# dengen1.net
KiCad netlist of a schematic drawn in EAGLE
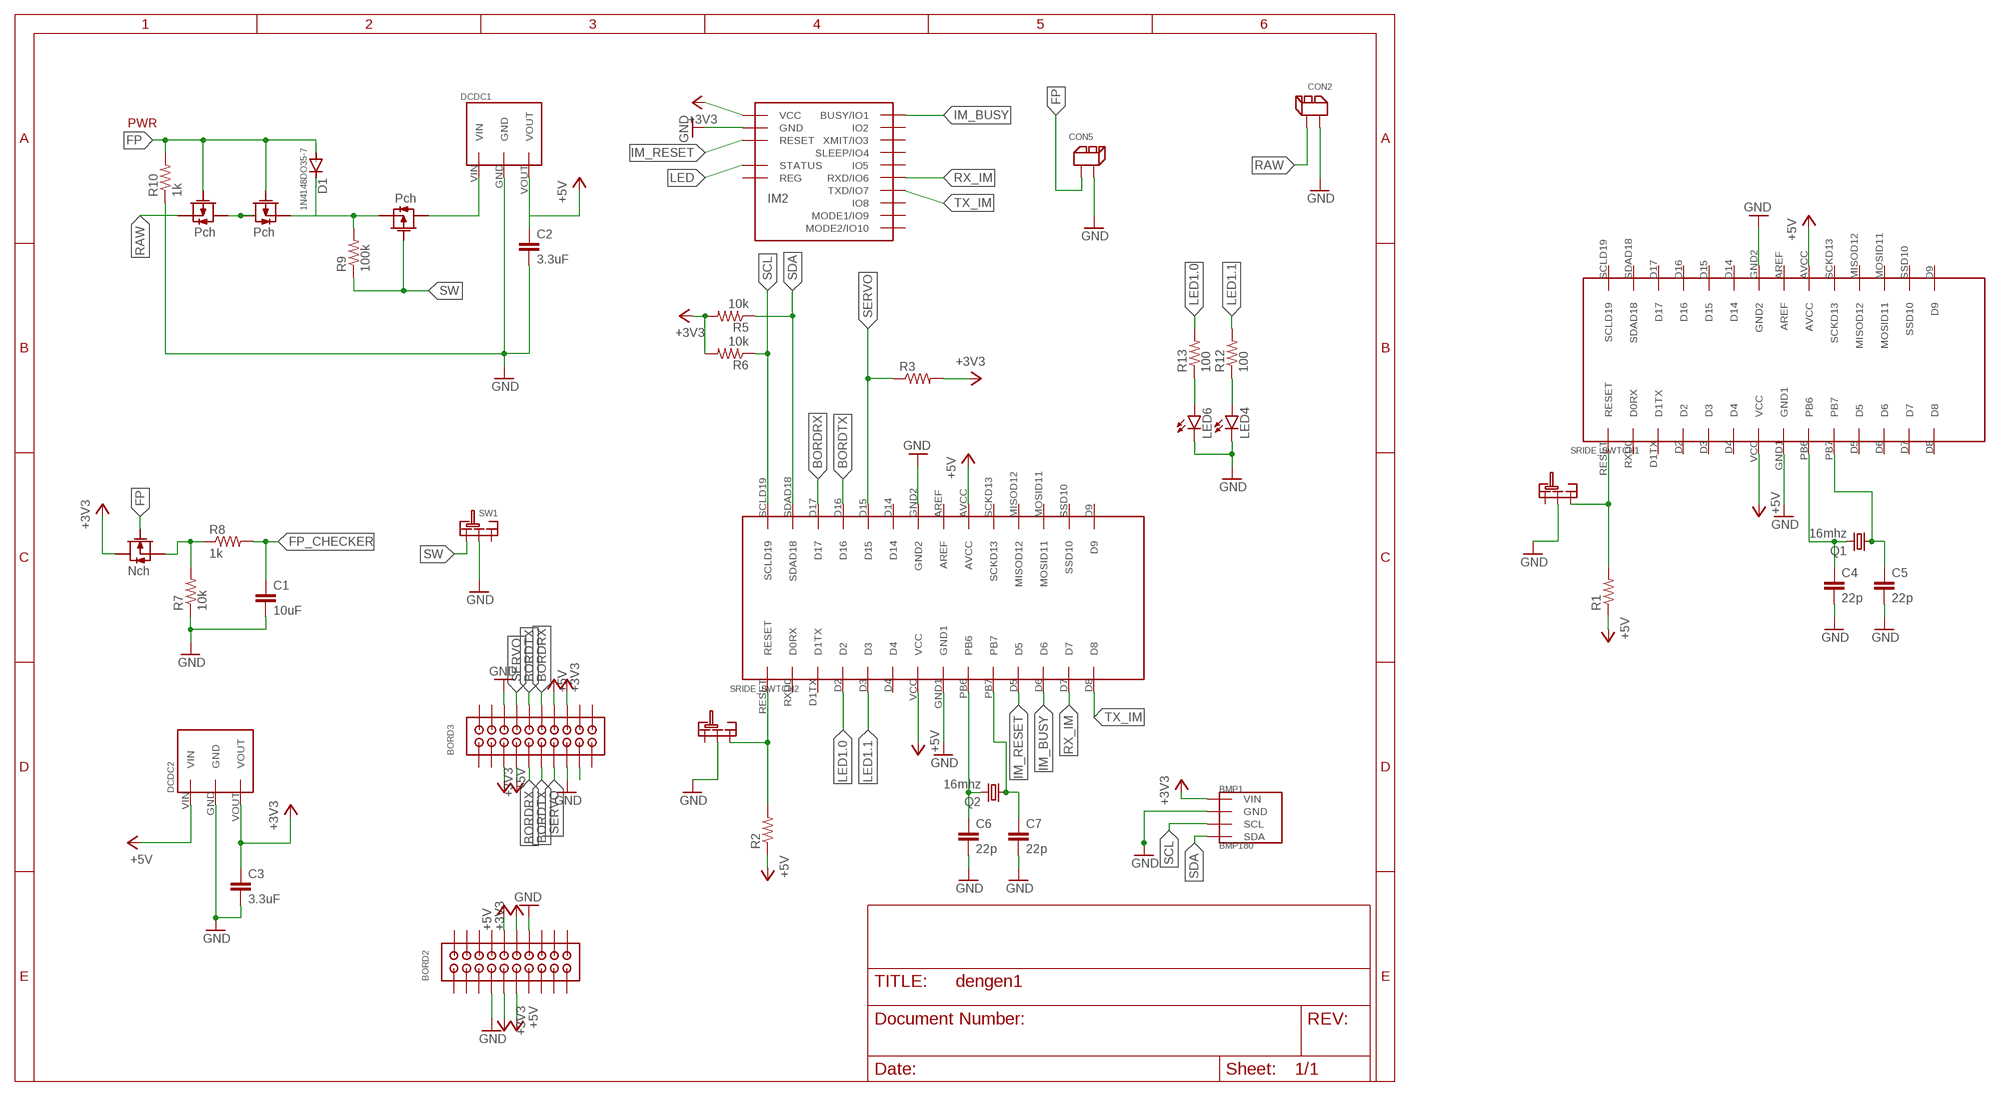
[diagram p0: schematic, sheet 1]

(export (version "E")
  (design (tool "Eeschema 10.0.6"))
  (components
    (comp (ref "BMP1")
      (value "BMP180")
      (footprint "eagle-import:GY-68")
      (libsource (lib "eagle-import") (part "BMP180"))
    )
    (comp (ref "BORD2")
      (value "2X10")
      (footprint "eagle-import:2X10")
      (libsource (lib "eagle-import") (part "2X10"))
    )
    (comp (ref "BORD3")
      (value "2X10")
      (footprint "eagle-import:2X10")
      (libsource (lib "eagle-import") (part "2X10"))
    )
    (comp (ref "C1")
      (value "10uF")
      (footprint "eagle-import:C025-024X044")
      (libsource (lib "eagle-import") (part "C-EU025-024X044"))
    )
    (comp (ref "C2")
      (value "3.3uF")
      (footprint "eagle-import:C025-024X044")
      (libsource (lib "eagle-import") (part "C-EU025-024X044"))
    )
    (comp (ref "C3")
      (value "3.3uF")
      (footprint "eagle-import:C025-024X044")
      (libsource (lib "eagle-import") (part "C-EU025-024X044"))
    )
    (comp (ref "C4")
      (value "22p")
      (footprint "eagle-import:C025-024X044")
      (libsource (lib "eagle-import") (part "C-EU025-024X044"))
    )
    (comp (ref "C5")
      (value "22p")
      (footprint "eagle-import:C025-024X044")
      (libsource (lib "eagle-import") (part "C-EU025-024X044"))
    )
    (comp (ref "C6")
      (value "22p")
      (footprint "eagle-import:C025-024X044")
      (libsource (lib "eagle-import") (part "C-EU025-024X044"))
    )
    (comp (ref "C7")
      (value "22p")
      (footprint "eagle-import:C025-024X044")
      (libsource (lib "eagle-import") (part "C-EU025-024X044"))
    )
    (comp (ref "CON2")
      (value "2PIN")
      (footprint "eagle-import:2PIN")
      (libsource (lib "eagle-import") (part "2PIN"))
    )
    (comp (ref "CON5")
      (value "2PIN")
      (footprint "eagle-import:2PIN")
      (libsource (lib "eagle-import") (part "2PIN"))
    )
    (comp (ref "D1")
      (value "1N4148DO35-7")
      (footprint "eagle-import:DO35-7")
      (libsource (lib "eagle-import") (part "1N4148DO35-7"))
    )
    (comp (ref "DCDC1")
      (value "5V1A_M78AR05-1")
      (footprint "eagle-import:5V1A_M78AR05-1")
      (libsource (lib "eagle-import") (part "5V1A_M78AR05-1"))
    )
    (comp (ref "DCDC2")
      (value "3.3V1A_M78AR033-1")
      (footprint "eagle-import:3.3V1A_M78AR033-1")
      (libsource (lib "eagle-import") (part "3.3V1A_M78AR033-1"))
    )
    (comp (ref "IM2")
      (value "IM920_IM920C")
      (footprint "eagle-import:IM920_IM920C")
      (libsource (lib "eagle-import") (part "IM920_IM920C"))
    )
    (comp (ref "LED4")
      (value "LED5MM")
      (footprint "eagle-import:LED5MM")
      (libsource (lib "eagle-import") (part "LED5MM"))
    )
    (comp (ref "LED6")
      (value "LED5MM")
      (footprint "eagle-import:LED5MM")
      (libsource (lib "eagle-import") (part "LED5MM"))
    )
    (comp (ref "Q1")
      (value "16mhz")
      (footprint "eagle-import:HC49_S")
      (libsource (lib "eagle-import") (part "CRYSTALHC49S"))
    )
    (comp (ref "Q2")
      (value "16mhz")
      (footprint "eagle-import:HC49_S")
      (libsource (lib "eagle-import") (part "CRYSTALHC49S"))
    )
    (comp (ref "R1")
      (value "R-US_0204/7")
      (footprint "eagle-import:0204_7")
      (libsource (lib "eagle-import") (part "R-US_0204/7"))
    )
    (comp (ref "R2")
      (value "R-US_0204/7")
      (footprint "eagle-import:0204_7")
      (libsource (lib "eagle-import") (part "R-US_0204/7"))
    )
    (comp (ref "R3")
      (value "R-US_0204/7")
      (footprint "eagle-import:0204_7")
      (libsource (lib "eagle-import") (part "R-US_0204/7"))
    )
    (comp (ref "R5")
      (value "10k")
      (footprint "eagle-import:0204_7")
      (libsource (lib "eagle-import") (part "R-US_0204/7"))
    )
    (comp (ref "R6")
      (value "10k")
      (footprint "eagle-import:0204_7")
      (libsource (lib "eagle-import") (part "R-US_0204/7"))
    )
    (comp (ref "R7")
      (value "10k")
      (footprint "eagle-import:0204_7")
      (libsource (lib "eagle-import") (part "R-US_0204/7"))
    )
    (comp (ref "R8")
      (value "1k")
      (footprint "eagle-import:0204_7")
      (libsource (lib "eagle-import") (part "R-US_0204/7"))
    )
    (comp (ref "R9")
      (value "100k")
      (footprint "eagle-import:0204_7")
      (libsource (lib "eagle-import") (part "R-US_0204/7"))
    )
    (comp (ref "R10")
      (value "1k")
      (footprint "eagle-import:0204_7")
      (libsource (lib "eagle-import") (part "R-US_0204/7"))
    )
    (comp (ref "R12")
      (value "100")
      (footprint "eagle-import:0204_7")
      (libsource (lib "eagle-import") (part "R-US_0204/7"))
    )
    (comp (ref "R13")
      (value "100")
      (footprint "eagle-import:0204_7")
      (libsource (lib "eagle-import") (part "R-US_0204/7"))
    )
    (comp (ref "SRIDE_SWTCH1")
      (value "SRIDE_SWITCH")
      (footprint "eagle-import:SRIDE_SWITCH")
      (libsource (lib "eagle-import") (part "SRIDE_SWITCH"))
    )
    (comp (ref "SRIDE_SWTCH2")
      (value "SRIDE_SWITCH")
      (footprint "eagle-import:SRIDE_SWITCH")
      (libsource (lib "eagle-import") (part "SRIDE_SWITCH"))
    )
    (comp (ref "SW1")
      (value "SRIDE_SWITCH")
      (footprint "eagle-import:SRIDE_SWITCH")
      (libsource (lib "eagle-import") (part "SRIDE_SWITCH"))
    )
    (comp (ref "U$1")
      (value "ATMEGA238P")
      (footprint "eagle-import:ATMEGA328P")
      (libsource (lib "eagle-import") (part "ATMEGA238P"))
    )
    (comp (ref "U$2")
      (value "2SJ681-PCH")
      (footprint "eagle-import:2SJ681")
      (libsource (lib "eagle-import") (part "2SJ681-PCH"))
    )
    (comp (ref "U$3")
      (value "2SK4017-NCH")
      (footprint "eagle-import:2SK4017")
      (libsource (lib "eagle-import") (part "2SK4017-NCH"))
    )
    (comp (ref "U$4")
      (value "2SJ681-PCH")
      (footprint "eagle-import:2SJ681")
      (libsource (lib "eagle-import") (part "2SJ681-PCH"))
    )
    (comp (ref "U$5")
      (value "2SJ681-PCH")
      (footprint "eagle-import:2SJ681")
      (libsource (lib "eagle-import") (part "2SJ681-PCH"))
    )
    (comp (ref "U$6")
      (value "ATMEGA238P")
      (footprint "eagle-import:ATMEGA328P")
      (libsource (lib "eagle-import") (part "ATMEGA238P"))
    )
  )
  (nets
    (net (code "1") (name "+3V3") (class "Default")
      (node (ref "BMP1") (pin "P1") (pinfunction "VIN_P1") (pintype "bidirectional"))
      (node (ref "BORD2") (pin "P$12") (pinfunction "P$12_P$12") (pintype "bidirectional"))
      (node (ref "BORD2") (pin "P$9") (pinfunction "P$9_P$9") (pintype "bidirectional"))
      (node (ref "BORD3") (pin "P$16") (pinfunction "P$16_P$16") (pintype "bidirectional"))
      (node (ref "BORD3") (pin "P$5") (pinfunction "P$5_P$5") (pintype "bidirectional"))
      (node (ref "C3") (pin "1") (pinfunction "1_1") (pintype "passive"))
      (node (ref "DCDC2") (pin "VOUT") (pinfunction "VOUT_VOUT") (pintype "bidirectional"))
      (node (ref "IM2") (pin "$P17") (pinfunction "VCC_$P17") (pintype "bidirectional"))
      (node (ref "R3") (pin "2") (pinfunction "2_2") (pintype "passive"))
      (node (ref "R5") (pin "2") (pinfunction "2_2") (pintype "passive"))
      (node (ref "R6") (pin "2") (pinfunction "2_2") (pintype "passive"))
      (node (ref "U$3") (pin "DRAIN") (pinfunction "DRAIN_DRAIN") (pintype "bidirectional"))
    )
    (net (code "2") (name "+5V") (class "Default")
      (node (ref "BORD2") (pin "P$10") (pinfunction "P$10_P$10") (pintype "bidirectional"))
      (node (ref "BORD2") (pin "P$11") (pinfunction "P$11_P$11") (pintype "bidirectional"))
      (node (ref "BORD3") (pin "P$14") (pinfunction "P$14_P$14") (pintype "bidirectional"))
      (node (ref "BORD3") (pin "P$7") (pinfunction "P$7_P$7") (pintype "bidirectional"))
      (node (ref "C2") (pin "1") (pinfunction "1_1") (pintype "passive"))
      (node (ref "DCDC1") (pin "VOUT") (pinfunction "VOUT_VOUT") (pintype "bidirectional"))
      (node (ref "DCDC2") (pin "VIN") (pinfunction "VIN_VIN") (pintype "bidirectional"))
      (node (ref "R1") (pin "1") (pinfunction "1_1") (pintype "passive"))
      (node (ref "R2") (pin "1") (pinfunction "1_1") (pintype "passive"))
      (node (ref "U$1") (pin "AVCC") (pinfunction "AVCC_AVCC") (pintype "bidirectional"))
      (node (ref "U$1") (pin "VCC") (pinfunction "VCC_VCC") (pintype "bidirectional"))
      (node (ref "U$6") (pin "AVCC") (pinfunction "AVCC_AVCC") (pintype "bidirectional"))
      (node (ref "U$6") (pin "VCC") (pinfunction "VCC_VCC") (pintype "bidirectional"))
    )
    (net (code "3") (name "BORDRX") (class "Default")
      (node (ref "BORD3") (pin "P$12") (pinfunction "P$12_P$12") (pintype "bidirectional"))
      (node (ref "BORD3") (pin "P$9") (pinfunction "P$9_P$9") (pintype "bidirectional"))
      (node (ref "U$6") (pin "D17") (pinfunction "D17_D17") (pintype "bidirectional"))
    )
    (net (code "4") (name "BORDTX") (class "Default")
      (node (ref "BORD3") (pin "P$10") (pinfunction "P$10_P$10") (pintype "bidirectional"))
      (node (ref "BORD3") (pin "P$11") (pinfunction "P$11_P$11") (pintype "bidirectional"))
      (node (ref "U$6") (pin "D16") (pinfunction "D16_D16") (pintype "bidirectional"))
    )
    (net (code "5") (name "FP") (class "Default")
      (node (ref "CON5") (pin "P$1") (pinfunction "P$1_P$1") (pintype "bidirectional"))
      (node (ref "D1") (pin "A") (pinfunction "A_A") (pintype "passive"))
      (node (ref "R10") (pin "2") (pinfunction "2_2") (pintype "passive"))
      (node (ref "U$2") (pin "GATE") (pinfunction "GATE_GATE") (pintype "bidirectional"))
      (node (ref "U$3") (pin "GATE") (pinfunction "GATE_GATE") (pintype "bidirectional"))
      (node (ref "U$4") (pin "GATE") (pinfunction "GATE_GATE") (pintype "bidirectional"))
    )
    (net (code "6") (name "FP_CHECKER") (class "Default")
      (node (ref "C1") (pin "1") (pinfunction "1_1") (pintype "passive"))
      (node (ref "R8") (pin "2") (pinfunction "2_2") (pintype "passive"))
    )
    (net (code "7") (name "GND") (class "Default")
      (node (ref "BMP1") (pin "P2") (pinfunction "GND_P2") (pintype "bidirectional"))
      (node (ref "BORD2") (pin "P$14") (pinfunction "P$14_P$14") (pintype "bidirectional"))
      (node (ref "BORD2") (pin "P$7") (pinfunction "P$7_P$7") (pintype "bidirectional"))
      (node (ref "BORD3") (pin "P$15") (pinfunction "P$15_P$15") (pintype "bidirectional"))
      (node (ref "BORD3") (pin "P$6") (pinfunction "P$6_P$6") (pintype "bidirectional"))
      (node (ref "C1") (pin "2") (pinfunction "2_2") (pintype "passive"))
      (node (ref "C2") (pin "2") (pinfunction "2_2") (pintype "passive"))
      (node (ref "C3") (pin "2") (pinfunction "2_2") (pintype "passive"))
      (node (ref "C4") (pin "2") (pinfunction "2_2") (pintype "passive"))
      (node (ref "C5") (pin "2") (pinfunction "2_2") (pintype "passive"))
      (node (ref "C6") (pin "2") (pinfunction "2_2") (pintype "passive"))
      (node (ref "C7") (pin "2") (pinfunction "2_2") (pintype "passive"))
      (node (ref "CON2") (pin "P$1") (pinfunction "P$1_P$1") (pintype "bidirectional"))
      (node (ref "CON5") (pin "P$2") (pinfunction "P$2_P$2") (pintype "bidirectional"))
      (node (ref "DCDC1") (pin "GND") (pinfunction "GND_GND") (pintype "bidirectional"))
      (node (ref "DCDC2") (pin "GND") (pinfunction "GND_GND") (pintype "bidirectional"))
      (node (ref "IM2") (pin "$P18") (pinfunction "GND_$P18") (pintype "bidirectional"))
      (node (ref "LED4") (pin "K") (pinfunction "C_K") (pintype "passive"))
      (node (ref "LED6") (pin "K") (pinfunction "C_K") (pintype "passive"))
      (node (ref "R10") (pin "1") (pinfunction "1_1") (pintype "passive"))
      (node (ref "R7") (pin "1") (pinfunction "1_1") (pintype "passive"))
      (node (ref "SRIDE_SWTCH1") (pin "LR") (pinfunction "LR_LR") (pintype "bidirectional"))
      (node (ref "SRIDE_SWTCH2") (pin "LR") (pinfunction "LR_LR") (pintype "bidirectional"))
      (node (ref "SW1") (pin "LR") (pinfunction "LR_LR") (pintype "bidirectional"))
      (node (ref "U$1") (pin "GND1") (pinfunction "GND1_GND1") (pintype "bidirectional"))
      (node (ref "U$1") (pin "GND2") (pinfunction "GND2_GND2") (pintype "bidirectional"))
      (node (ref "U$6") (pin "GND1") (pinfunction "GND1_GND1") (pintype "bidirectional"))
      (node (ref "U$6") (pin "GND2") (pinfunction "GND2_GND2") (pintype "bidirectional"))
    )
    (net (code "8") (name "IM_BUSY") (class "Default")
      (node (ref "IM2") (pin "$P1") (pinfunction "BUSY/IO1_$P1") (pintype "bidirectional"))
      (node (ref "U$6") (pin "D6") (pinfunction "D6_D6") (pintype "bidirectional"))
    )
    (net (code "9") (name "IM_RESET") (class "Default")
      (node (ref "IM2") (pin "$P19") (pinfunction "RESET_$P19") (pintype "bidirectional"))
      (node (ref "U$6") (pin "D5") (pinfunction "D5_D5") (pintype "bidirectional"))
    )
    (net (code "10") (name "LED") (class "Default")
      (node (ref "IM2") (pin "$P15") (pinfunction "STATUS_$P15") (pintype "bidirectional"))
    )
    (net (code "11") (name "LED1.0") (class "Default")
      (node (ref "R13") (pin "2") (pinfunction "2_2") (pintype "passive"))
      (node (ref "U$6") (pin "D2") (pinfunction "D2_D2") (pintype "bidirectional"))
    )
    (net (code "12") (name "LED1.1") (class "Default")
      (node (ref "R12") (pin "2") (pinfunction "2_2") (pintype "passive"))
      (node (ref "U$6") (pin "D3") (pinfunction "D3_D3") (pintype "bidirectional"))
    )
    (net (code "13") (name "Net-(C4-Pad1)") (class "Default")
      (node (ref "C4") (pin "1") (pinfunction "1_1") (pintype "passive"))
      (node (ref "Q1") (pin "2") (pinfunction "2_2") (pintype "passive"))
      (node (ref "U$1") (pin "PB6") (pinfunction "PB6_PB6") (pintype "bidirectional"))
    )
    (net (code "14") (name "Net-(C5-Pad1)") (class "Default")
      (node (ref "C5") (pin "1") (pinfunction "1_1") (pintype "passive"))
      (node (ref "Q1") (pin "1") (pinfunction "1_1") (pintype "passive"))
      (node (ref "U$1") (pin "PB7") (pinfunction "PB7_PB7") (pintype "bidirectional"))
    )
    (net (code "15") (name "Net-(C6-Pad1)") (class "Default")
      (node (ref "C6") (pin "1") (pinfunction "1_1") (pintype "passive"))
      (node (ref "Q2") (pin "2") (pinfunction "2_2") (pintype "passive"))
      (node (ref "U$6") (pin "PB6") (pinfunction "PB6_PB6") (pintype "bidirectional"))
    )
    (net (code "16") (name "Net-(C7-Pad1)") (class "Default")
      (node (ref "C7") (pin "1") (pinfunction "1_1") (pintype "passive"))
      (node (ref "Q2") (pin "1") (pinfunction "1_1") (pintype "passive"))
      (node (ref "U$6") (pin "PB7") (pinfunction "PB7_PB7") (pintype "bidirectional"))
    )
    (net (code "17") (name "Net-(D1-PadC)") (class "Default")
      (node (ref "D1") (pin "C") (pinfunction "C_C") (pintype "passive"))
      (node (ref "R9") (pin "2") (pinfunction "2_2") (pintype "passive"))
      (node (ref "U$4") (pin "SOURCE") (pinfunction "SOURCE_SOURCE") (pintype "bidirectional"))
      (node (ref "U$5") (pin "SOURCE") (pinfunction "SOURCE_SOURCE") (pintype "bidirectional"))
    )
    (net (code "18") (name "Net-(DCDC1-PadVIN)") (class "Default")
      (node (ref "DCDC1") (pin "VIN") (pinfunction "VIN_VIN") (pintype "bidirectional"))
      (node (ref "U$5") (pin "DRAIN") (pinfunction "DRAIN_DRAIN") (pintype "bidirectional"))
    )
    (net (code "19") (name "Net-(LED4-PadA)") (class "Default")
      (node (ref "LED4") (pin "A") (pinfunction "A_A") (pintype "passive"))
      (node (ref "R12") (pin "1") (pinfunction "1_1") (pintype "passive"))
    )
    (net (code "20") (name "Net-(LED6-PadA)") (class "Default")
      (node (ref "LED6") (pin "A") (pinfunction "A_A") (pintype "passive"))
      (node (ref "R13") (pin "1") (pinfunction "1_1") (pintype "passive"))
    )
    (net (code "21") (name "Net-(R1-Pad2)") (class "Default")
      (node (ref "R1") (pin "2") (pinfunction "2_2") (pintype "passive"))
      (node (ref "SRIDE_SWTCH1") (pin "R") (pinfunction "R_R") (pintype "bidirectional"))
      (node (ref "U$1") (pin "RESET") (pinfunction "RESET_RESET") (pintype "bidirectional"))
    )
    (net (code "22") (name "Net-(R2-Pad2)") (class "Default")
      (node (ref "R2") (pin "2") (pinfunction "2_2") (pintype "passive"))
      (node (ref "SRIDE_SWTCH2") (pin "R") (pinfunction "R_R") (pintype "bidirectional"))
      (node (ref "U$6") (pin "RESET") (pinfunction "RESET_RESET") (pintype "bidirectional"))
    )
    (net (code "23") (name "Net-(R7-Pad2)") (class "Default")
      (node (ref "R7") (pin "2") (pinfunction "2_2") (pintype "passive"))
      (node (ref "R8") (pin "1") (pinfunction "1_1") (pintype "passive"))
      (node (ref "U$3") (pin "SOURCE") (pinfunction "SOURCE_SOURCE") (pintype "bidirectional"))
    )
    (net (code "24") (name "Net-(U$2-PadDRAIN)") (class "Default")
      (node (ref "U$2") (pin "DRAIN") (pinfunction "DRAIN_DRAIN") (pintype "bidirectional"))
      (node (ref "U$4") (pin "DRAIN") (pinfunction "DRAIN_DRAIN") (pintype "bidirectional"))
    )
    (net (code "25") (name "RAW") (class "Default")
      (node (ref "CON2") (pin "P$2") (pinfunction "P$2_P$2") (pintype "bidirectional"))
      (node (ref "U$2") (pin "SOURCE") (pinfunction "SOURCE_SOURCE") (pintype "bidirectional"))
    )
    (net (code "26") (name "RX_IM") (class "Default")
      (node (ref "IM2") (pin "$P6") (pinfunction "RXD/IO6_$P6") (pintype "bidirectional"))
      (node (ref "U$6") (pin "D7") (pinfunction "D7_D7") (pintype "bidirectional"))
    )
    (net (code "27") (name "SCL") (class "Default")
      (node (ref "BMP1") (pin "P3") (pinfunction "SCL_P3") (pintype "bidirectional"))
      (node (ref "R6") (pin "1") (pinfunction "1_1") (pintype "passive"))
      (node (ref "U$6") (pin "SCLD19") (pinfunction "SCLD19_SCLD19") (pintype "bidirectional"))
    )
    (net (code "28") (name "SDA") (class "Default")
      (node (ref "BMP1") (pin "P4") (pinfunction "SDA_P4") (pintype "bidirectional"))
      (node (ref "R5") (pin "1") (pinfunction "1_1") (pintype "passive"))
      (node (ref "U$6") (pin "SDAD18") (pinfunction "SDAD18_SDAD18") (pintype "bidirectional"))
    )
    (net (code "29") (name "SERVO") (class "Default")
      (node (ref "BORD3") (pin "P$13") (pinfunction "P$13_P$13") (pintype "bidirectional"))
      (node (ref "BORD3") (pin "P$8") (pinfunction "P$8_P$8") (pintype "bidirectional"))
      (node (ref "R3") (pin "1") (pinfunction "1_1") (pintype "passive"))
      (node (ref "U$6") (pin "D15") (pinfunction "D15_D15") (pintype "bidirectional"))
    )
    (net (code "30") (name "SW") (class "Default")
      (node (ref "R9") (pin "1") (pinfunction "1_1") (pintype "passive"))
      (node (ref "SW1") (pin "L") (pinfunction "L_L") (pintype "bidirectional"))
      (node (ref "U$5") (pin "GATE") (pinfunction "GATE_GATE") (pintype "bidirectional"))
    )
    (net (code "31") (name "TX_IM") (class "Default")
      (node (ref "IM2") (pin "$P7") (pinfunction "TXD/IO7_$P7") (pintype "bidirectional"))
      (node (ref "U$6") (pin "D8") (pinfunction "D8_D8") (pintype "bidirectional"))
    )
    (net (code "32") (name "unconnected-(BORD2-PadP$1)") (class "Default")
      (node (ref "BORD2") (pin "P$1") (pinfunction "P$1_P$1") (pintype "bidirectional"))
    )
    (net (code "33") (name "unconnected-(BORD2-PadP$2)") (class "Default")
      (node (ref "BORD2") (pin "P$2") (pinfunction "P$2_P$2") (pintype "bidirectional"))
    )
    (net (code "34") (name "unconnected-(BORD2-PadP$3)") (class "Default")
      (node (ref "BORD2") (pin "P$3") (pinfunction "P$3_P$3") (pintype "bidirectional"))
    )
    (net (code "35") (name "unconnected-(BORD2-PadP$4)") (class "Default")
      (node (ref "BORD2") (pin "P$4") (pinfunction "P$4_P$4") (pintype "bidirectional"))
    )
    (net (code "36") (name "unconnected-(BORD2-PadP$5)") (class "Default")
      (node (ref "BORD2") (pin "P$5") (pinfunction "P$5_P$5") (pintype "bidirectional"))
    )
    (net (code "37") (name "unconnected-(BORD2-PadP$6)") (class "Default")
      (node (ref "BORD2") (pin "P$6") (pinfunction "P$6_P$6") (pintype "bidirectional"))
    )
    (net (code "38") (name "unconnected-(BORD2-PadP$8)") (class "Default")
      (node (ref "BORD2") (pin "P$8") (pinfunction "P$8_P$8") (pintype "bidirectional"))
    )
    (net (code "39") (name "unconnected-(BORD2-PadP$13)") (class "Default")
      (node (ref "BORD2") (pin "P$13") (pinfunction "P$13_P$13") (pintype "bidirectional"))
    )
    (net (code "40") (name "unconnected-(BORD2-PadP$15)") (class "Default")
      (node (ref "BORD2") (pin "P$15") (pinfunction "P$15_P$15") (pintype "bidirectional"))
    )
    (net (code "41") (name "unconnected-(BORD2-PadP$16)") (class "Default")
      (node (ref "BORD2") (pin "P$16") (pinfunction "P$16_P$16") (pintype "bidirectional"))
    )
    (net (code "42") (name "unconnected-(BORD2-PadP$17)") (class "Default")
      (node (ref "BORD2") (pin "P$17") (pinfunction "P$17_P$17") (pintype "bidirectional"))
    )
    (net (code "43") (name "unconnected-(BORD2-PadP$18)") (class "Default")
      (node (ref "BORD2") (pin "P$18") (pinfunction "P$18_P$18") (pintype "bidirectional"))
    )
    (net (code "44") (name "unconnected-(BORD2-PadP$19)") (class "Default")
      (node (ref "BORD2") (pin "P$19") (pinfunction "P$19_P$19") (pintype "bidirectional"))
    )
    (net (code "45") (name "unconnected-(BORD2-PadP$20)") (class "Default")
      (node (ref "BORD2") (pin "P$20") (pinfunction "P$20_P$20") (pintype "bidirectional"))
    )
    (net (code "46") (name "unconnected-(BORD3-PadP$1)") (class "Default")
      (node (ref "BORD3") (pin "P$1") (pinfunction "P$1_P$1") (pintype "bidirectional"))
    )
    (net (code "47") (name "unconnected-(BORD3-PadP$2)") (class "Default")
      (node (ref "BORD3") (pin "P$2") (pinfunction "P$2_P$2") (pintype "bidirectional"))
    )
    (net (code "48") (name "unconnected-(BORD3-PadP$3)") (class "Default")
      (node (ref "BORD3") (pin "P$3") (pinfunction "P$3_P$3") (pintype "bidirectional"))
    )
    (net (code "49") (name "unconnected-(BORD3-PadP$4)") (class "Default")
      (node (ref "BORD3") (pin "P$4") (pinfunction "P$4_P$4") (pintype "bidirectional"))
    )
    (net (code "50") (name "unconnected-(BORD3-PadP$17)") (class "Default")
      (node (ref "BORD3") (pin "P$17") (pinfunction "P$17_P$17") (pintype "bidirectional"))
    )
    (net (code "51") (name "unconnected-(BORD3-PadP$18)") (class "Default")
      (node (ref "BORD3") (pin "P$18") (pinfunction "P$18_P$18") (pintype "bidirectional"))
    )
    (net (code "52") (name "unconnected-(BORD3-PadP$19)") (class "Default")
      (node (ref "BORD3") (pin "P$19") (pinfunction "P$19_P$19") (pintype "bidirectional"))
    )
    (net (code "53") (name "unconnected-(BORD3-PadP$20)") (class "Default")
      (node (ref "BORD3") (pin "P$20") (pinfunction "P$20_P$20") (pintype "bidirectional"))
    )
    (net (code "54") (name "unconnected-(IM2-IO2-Pad$P2)") (class "Default")
      (node (ref "IM2") (pin "$P2") (pinfunction "IO2_$P2") (pintype "bidirectional"))
    )
    (net (code "55") (name "unconnected-(IM2-IO5-Pad$P5)") (class "Default")
      (node (ref "IM2") (pin "$P5") (pinfunction "IO5_$P5") (pintype "bidirectional"))
    )
    (net (code "56") (name "unconnected-(IM2-IO8-Pad$P8)") (class "Default")
      (node (ref "IM2") (pin "$P8") (pinfunction "IO8_$P8") (pintype "bidirectional"))
    )
    (net (code "57") (name "unconnected-(IM2-MODE1{slash}IO9-Pad$P9)") (class "Default")
      (node (ref "IM2") (pin "$P9") (pinfunction "MODE1/IO9_$P9") (pintype "bidirectional"))
    )
    (net (code "58") (name "unconnected-(IM2-MODE2{slash}IO10-Pad$P10)") (class "Default")
      (node (ref "IM2") (pin "$P10") (pinfunction "MODE2/IO10_$P10") (pintype "bidirectional"))
    )
    (net (code "59") (name "unconnected-(IM2-REG-Pad$P16)") (class "Default")
      (node (ref "IM2") (pin "$P16") (pinfunction "REG_$P16") (pintype "bidirectional"))
    )
    (net (code "60") (name "unconnected-(IM2-SLEEP{slash}IO4-Pad$P4)") (class "Default")
      (node (ref "IM2") (pin "$P4") (pinfunction "SLEEP/IO4_$P4") (pintype "bidirectional"))
    )
    (net (code "61") (name "unconnected-(IM2-XMIT{slash}IO3-Pad$P3)") (class "Default")
      (node (ref "IM2") (pin "$P3") (pinfunction "XMIT/IO3_$P3") (pintype "bidirectional"))
    )
    (net (code "62") (name "unconnected-(SRIDE_SWTCH1-PadL)") (class "Default")
      (node (ref "SRIDE_SWTCH1") (pin "L") (pinfunction "L_L") (pintype "bidirectional"))
    )
    (net (code "63") (name "unconnected-(SRIDE_SWTCH2-PadL)") (class "Default")
      (node (ref "SRIDE_SWTCH2") (pin "L") (pinfunction "L_L") (pintype "bidirectional"))
    )
    (net (code "64") (name "unconnected-(SW1-PadR)") (class "Default")
      (node (ref "SW1") (pin "R") (pinfunction "R_R") (pintype "bidirectional"))
    )
    (net (code "65") (name "unconnected-(U$1-D0RX-PadRXD0)") (class "Default")
      (node (ref "U$1") (pin "RXD0") (pinfunction "D0RX_RXD0") (pintype "bidirectional"))
    )
    (net (code "66") (name "unconnected-(U$1-PadAREF)") (class "Default")
      (node (ref "U$1") (pin "AREF") (pinfunction "AREF_AREF") (pintype "bidirectional"))
    )
    (net (code "67") (name "unconnected-(U$1-PadD1TX)") (class "Default")
      (node (ref "U$1") (pin "D1TX") (pinfunction "D1TX_D1TX") (pintype "bidirectional"))
    )
    (net (code "68") (name "unconnected-(U$1-PadD2)") (class "Default")
      (node (ref "U$1") (pin "D2") (pinfunction "D2_D2") (pintype "bidirectional"))
    )
    (net (code "69") (name "unconnected-(U$1-PadD3)") (class "Default")
      (node (ref "U$1") (pin "D3") (pinfunction "D3_D3") (pintype "bidirectional"))
    )
    (net (code "70") (name "unconnected-(U$1-PadD4)") (class "Default")
      (node (ref "U$1") (pin "D4") (pinfunction "D4_D4") (pintype "bidirectional"))
    )
    (net (code "71") (name "unconnected-(U$1-PadD5)") (class "Default")
      (node (ref "U$1") (pin "D5") (pinfunction "D5_D5") (pintype "bidirectional"))
    )
    (net (code "72") (name "unconnected-(U$1-PadD6)") (class "Default")
      (node (ref "U$1") (pin "D6") (pinfunction "D6_D6") (pintype "bidirectional"))
    )
    (net (code "73") (name "unconnected-(U$1-PadD7)") (class "Default")
      (node (ref "U$1") (pin "D7") (pinfunction "D7_D7") (pintype "bidirectional"))
    )
    (net (code "74") (name "unconnected-(U$1-PadD8)") (class "Default")
      (node (ref "U$1") (pin "D8") (pinfunction "D8_D8") (pintype "bidirectional"))
    )
    (net (code "75") (name "unconnected-(U$1-PadD9)") (class "Default")
      (node (ref "U$1") (pin "D9") (pinfunction "D9_D9") (pintype "bidirectional"))
    )
    (net (code "76") (name "unconnected-(U$1-PadD14)") (class "Default")
      (node (ref "U$1") (pin "D14") (pinfunction "D14_D14") (pintype "bidirectional"))
    )
    (net (code "77") (name "unconnected-(U$1-PadD15)") (class "Default")
      (node (ref "U$1") (pin "D15") (pinfunction "D15_D15") (pintype "bidirectional"))
    )
    (net (code "78") (name "unconnected-(U$1-PadD16)") (class "Default")
      (node (ref "U$1") (pin "D16") (pinfunction "D16_D16") (pintype "bidirectional"))
    )
    (net (code "79") (name "unconnected-(U$1-PadD17)") (class "Default")
      (node (ref "U$1") (pin "D17") (pinfunction "D17_D17") (pintype "bidirectional"))
    )
    (net (code "80") (name "unconnected-(U$1-PadMISOD12)") (class "Default")
      (node (ref "U$1") (pin "MISOD12") (pinfunction "MISOD12_MISOD12") (pintype "bidirectional"))
    )
    (net (code "81") (name "unconnected-(U$1-PadMOSID11)") (class "Default")
      (node (ref "U$1") (pin "MOSID11") (pinfunction "MOSID11_MOSID11") (pintype "bidirectional"))
    )
    (net (code "82") (name "unconnected-(U$1-PadSCKD13)") (class "Default")
      (node (ref "U$1") (pin "SCKD13") (pinfunction "SCKD13_SCKD13") (pintype "bidirectional"))
    )
    (net (code "83") (name "unconnected-(U$1-PadSCLD19)") (class "Default")
      (node (ref "U$1") (pin "SCLD19") (pinfunction "SCLD19_SCLD19") (pintype "bidirectional"))
    )
    (net (code "84") (name "unconnected-(U$1-PadSDAD18)") (class "Default")
      (node (ref "U$1") (pin "SDAD18") (pinfunction "SDAD18_SDAD18") (pintype "bidirectional"))
    )
    (net (code "85") (name "unconnected-(U$1-PadSSD10)") (class "Default")
      (node (ref "U$1") (pin "SSD10") (pinfunction "SSD10_SSD10") (pintype "bidirectional"))
    )
    (net (code "86") (name "unconnected-(U$6-D0RX-PadRXD0)") (class "Default")
      (node (ref "U$6") (pin "RXD0") (pinfunction "D0RX_RXD0") (pintype "bidirectional"))
    )
    (net (code "87") (name "unconnected-(U$6-PadAREF)") (class "Default")
      (node (ref "U$6") (pin "AREF") (pinfunction "AREF_AREF") (pintype "bidirectional"))
    )
    (net (code "88") (name "unconnected-(U$6-PadD1TX)") (class "Default")
      (node (ref "U$6") (pin "D1TX") (pinfunction "D1TX_D1TX") (pintype "bidirectional"))
    )
    (net (code "89") (name "unconnected-(U$6-PadD4)") (class "Default")
      (node (ref "U$6") (pin "D4") (pinfunction "D4_D4") (pintype "bidirectional"))
    )
    (net (code "90") (name "unconnected-(U$6-PadD9)") (class "Default")
      (node (ref "U$6") (pin "D9") (pinfunction "D9_D9") (pintype "bidirectional"))
    )
    (net (code "91") (name "unconnected-(U$6-PadD14)") (class "Default")
      (node (ref "U$6") (pin "D14") (pinfunction "D14_D14") (pintype "bidirectional"))
    )
    (net (code "92") (name "unconnected-(U$6-PadMISOD12)") (class "Default")
      (node (ref "U$6") (pin "MISOD12") (pinfunction "MISOD12_MISOD12") (pintype "bidirectional"))
    )
    (net (code "93") (name "unconnected-(U$6-PadMOSID11)") (class "Default")
      (node (ref "U$6") (pin "MOSID11") (pinfunction "MOSID11_MOSID11") (pintype "bidirectional"))
    )
    (net (code "94") (name "unconnected-(U$6-PadSCKD13)") (class "Default")
      (node (ref "U$6") (pin "SCKD13") (pinfunction "SCKD13_SCKD13") (pintype "bidirectional"))
    )
    (net (code "95") (name "unconnected-(U$6-PadSSD10)") (class "Default")
      (node (ref "U$6") (pin "SSD10") (pinfunction "SSD10_SSD10") (pintype "bidirectional"))
    )
  )
)
